# MSP430.net
KiCad netlist of a schematic drawn in Altium Designer
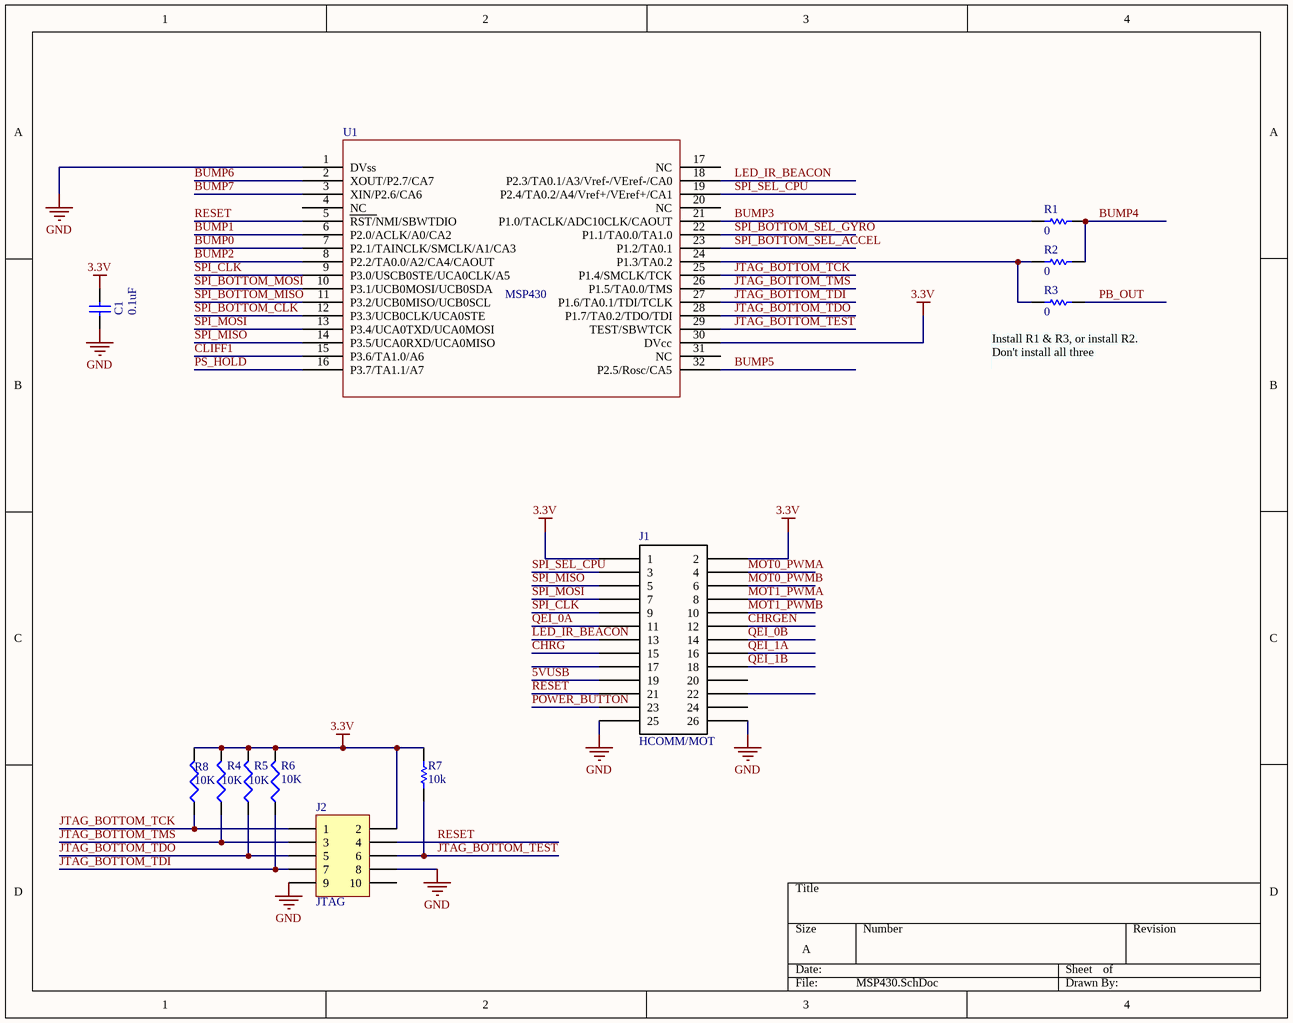
[diagram p0: MSP430.SchDoc]

(export (version "E")
  (design (tool "Eeschema 10.0.6"))
  (components
    (comp (ref "C1")
      (value "0.1uF")
      (footprint "CAPC1005L")
      (description "Capacitor (Semiconductor SIM Model)")
      (fields (field (name "Comment") "Cap Semi") (field (name "PUBLISHER") "Altium Limited"))
      (libsource (lib "Miscellaneous Devices") (part "Cap Semi"))
    )
    (comp (ref "J1")
      (value "HCOMM/MOT")
      (footprint "HeaderSM 13x2")
      (description "Header, 2X20, 50mil, IDC")
      (libsource (lib "mrone") (part "HCOMM/HMOT"))
    )
    (comp (ref "J2")
      (value "JTAG")
      (footprint "HDR2X5")
      (description "Header, 5-Pin, Dual row")
      (fields (field (name "PUBLISHER") "Altium Limited"))
      (libsource (lib "Miscellaneous Connectors") (part "Header 5X2"))
    )
    (comp (ref "R1")
      (value "0")
      (footprint "RESC1608L")
      (description "Semiconductor Resistor")
      (fields (field (name "Comment") "Res Semi") (field (name "PUBLISHER") "Altium Limited"))
      (libsource (lib "Miscellaneous Devices") (part "Res Semi"))
    )
    (comp (ref "R2")
      (value "0")
      (footprint "RESC1608L")
      (description "Semiconductor Resistor")
      (fields (field (name "Comment") "Res Semi") (field (name "PUBLISHER") "Altium Limited"))
      (libsource (lib "Miscellaneous Devices") (part "Res Semi"))
    )
    (comp (ref "R3")
      (value "0")
      (footprint "RESC1608L")
      (description "Semiconductor Resistor")
      (fields (field (name "Comment") "Res Semi") (field (name "PUBLISHER") "Altium Limited"))
      (libsource (lib "Miscellaneous Devices") (part "Res Semi"))
    )
    (comp (ref "R4")
      (value "10K")
      (footprint "RESC1608L")
      (description "Resistor")
      (fields (field (name "Comment") "Res3") (field (name "PUBLISHER") "Altium Limited"))
      (libsource (lib "Miscellaneous Devices") (part "Res3"))
    )
    (comp (ref "R5")
      (value "10K")
      (footprint "RESC1608L")
      (description "Resistor")
      (fields (field (name "Comment") "Res3") (field (name "PUBLISHER") "Altium Limited"))
      (libsource (lib "Miscellaneous Devices") (part "Res3"))
    )
    (comp (ref "R6")
      (value "10K")
      (footprint "RESC1608L")
      (description "Resistor")
      (fields (field (name "Comment") "Res3") (field (name "PUBLISHER") "Altium Limited"))
      (libsource (lib "Miscellaneous Devices") (part "Res3"))
    )
    (comp (ref "R7")
      (value "10k")
      (footprint "RESC1608L")
      (description "Semiconductor Resistor")
      (fields (field (name "Comment") "Res Semi") (field (name "PUBLISHER") "Altium Limited"))
      (libsource (lib "Miscellaneous Devices") (part "Res Semi"))
    )
    (comp (ref "R8")
      (value "10K")
      (footprint "RESC1608L")
      (description "Resistor")
      (fields (field (name "Comment") "Res3") (field (name "PUBLISHER") "Altium Limited"))
      (libsource (lib "Miscellaneous Devices") (part "Res3"))
    )
    (comp (ref "U1")
      (value "MSP430")
      (footprint "MSP430_32PIN")
      (libsource (lib "mrone") (part "MSP430_32pin"))
    )
  )
  (nets
    (net (code "1") (name "/5VUSB") (class "Default")
      (node (ref "J1") (pin "19") (pinfunction "19_19") (pintype "passive"))
    )
    (net (code "2") (name "/BUMP0") (class "Default")
      (node (ref "U1") (pin "7") (pinfunction "P2.1/TAINCLK/SMCLK/A1/CA3_7") (pintype "passive"))
    )
    (net (code "3") (name "/BUMP1") (class "Default")
      (node (ref "U1") (pin "6") (pinfunction "P2.0/ACLK/A0/CA2_6") (pintype "passive"))
    )
    (net (code "4") (name "/BUMP2") (class "Default")
      (node (ref "U1") (pin "8") (pinfunction "P2.2/TA0.0/A2/CA4/CAOUT_8") (pintype "passive"))
    )
    (net (code "5") (name "/BUMP3") (class "Default")
      (node (ref "R1") (pin "2") (pinfunction "2_2") (pintype "passive"))
      (node (ref "U1") (pin "21") (pinfunction "P1.0/TACLK/ADC10CLK/CAOUT_21") (pintype "passive"))
    )
    (net (code "6") (name "/BUMP4") (class "Default")
      (node (ref "R1") (pin "1") (pinfunction "1_1") (pintype "passive"))
      (node (ref "R2") (pin "1") (pinfunction "1_1") (pintype "passive"))
    )
    (net (code "7") (name "/BUMP5") (class "Default")
      (node (ref "U1") (pin "32") (pinfunction "P2.5/Rosc/CA5_32") (pintype "passive"))
    )
    (net (code "8") (name "/BUMP6") (class "Default")
      (node (ref "U1") (pin "2") (pinfunction "XOUT/P2.7/CA7_2") (pintype "passive"))
    )
    (net (code "9") (name "/BUMP7") (class "Default")
      (node (ref "U1") (pin "3") (pinfunction "XIN/P2.6/CA6_3") (pintype "passive"))
    )
    (net (code "10") (name "/CHRG") (class "Default")
      (node (ref "J1") (pin "15") (pinfunction "15_15") (pintype "passive"))
    )
    (net (code "11") (name "/CHRGEN") (class "Default")
      (node (ref "J1") (pin "12") (pinfunction "12_12") (pintype "passive"))
    )
    (net (code "12") (name "/CLIFF1") (class "Default")
      (node (ref "U1") (pin "15") (pinfunction "P3.6/TA1.0/A6_15") (pintype "passive"))
    )
    (net (code "13") (name "/JTAG_BOTTOM_TCK") (class "Default")
      (node (ref "J2") (pin "1") (pinfunction "1_1") (pintype "passive"))
      (node (ref "R8") (pin "1") (pinfunction "1_1") (pintype "passive"))
      (node (ref "U1") (pin "25") (pinfunction "P1.4/SMCLK/TCK_25") (pintype "passive"))
    )
    (net (code "14") (name "/JTAG_BOTTOM_TDI") (class "Default")
      (node (ref "J2") (pin "7") (pinfunction "7_7") (pintype "passive"))
      (node (ref "R6") (pin "1") (pinfunction "1_1") (pintype "passive"))
      (node (ref "U1") (pin "27") (pinfunction "P1.6/TA0.1/TDI/TCLK_27") (pintype "passive"))
    )
    (net (code "15") (name "/JTAG_BOTTOM_TDO") (class "Default")
      (node (ref "J2") (pin "5") (pinfunction "5_5") (pintype "passive"))
      (node (ref "R5") (pin "1") (pinfunction "1_1") (pintype "passive"))
      (node (ref "U1") (pin "28") (pinfunction "P1.7/TA0.2/TDO/TDI_28") (pintype "passive"))
    )
    (net (code "16") (name "/JTAG_BOTTOM_TEST") (class "Default")
      (node (ref "J2") (pin "6") (pinfunction "6_6") (pintype "passive"))
      (node (ref "R7") (pin "1") (pinfunction "1_1") (pintype "passive"))
      (node (ref "U1") (pin "29") (pinfunction "TEST/SBWTCK_29") (pintype "passive"))
    )
    (net (code "17") (name "/JTAG_BOTTOM_TMS") (class "Default")
      (node (ref "J2") (pin "3") (pinfunction "3_3") (pintype "passive"))
      (node (ref "R4") (pin "1") (pinfunction "1_1") (pintype "passive"))
      (node (ref "U1") (pin "26") (pinfunction "P1.5/TA0.0/TMS_26") (pintype "passive"))
    )
    (net (code "18") (name "/LED_IR_BEACON") (class "Default")
      (node (ref "J1") (pin "13") (pinfunction "13_13") (pintype "passive"))
      (node (ref "U1") (pin "18") (pinfunction "P2.3/TA0.1/A3/Vref-/VEref-/CA0_18") (pintype "passive"))
    )
    (net (code "19") (name "/MOT0_PWMA") (class "Default")
      (node (ref "J1") (pin "4") (pinfunction "4_4") (pintype "passive"))
    )
    (net (code "20") (name "/MOT0_PWMB") (class "Default")
      (node (ref "J1") (pin "6") (pinfunction "6_6") (pintype "passive"))
    )
    (net (code "21") (name "/MOT1_PWMA") (class "Default")
      (node (ref "J1") (pin "8") (pinfunction "8_8") (pintype "passive"))
    )
    (net (code "22") (name "/MOT1_PWMB") (class "Default")
      (node (ref "J1") (pin "10") (pinfunction "10_10") (pintype "passive"))
    )
    (net (code "23") (name "/PB_OUT") (class "Default")
      (node (ref "R3") (pin "1") (pinfunction "1_1") (pintype "passive"))
    )
    (net (code "24") (name "/POWER_BUTTON") (class "Default")
      (node (ref "J1") (pin "23") (pinfunction "23_23") (pintype "passive"))
    )
    (net (code "25") (name "/PS_HOLD") (class "Default")
      (node (ref "U1") (pin "16") (pinfunction "P3.7/TA1.1/A7_16") (pintype "passive"))
    )
    (net (code "26") (name "/QEI_0A") (class "Default")
      (node (ref "J1") (pin "11") (pinfunction "11_11") (pintype "passive"))
    )
    (net (code "27") (name "/QEI_0B") (class "Default")
      (node (ref "J1") (pin "14") (pinfunction "14_14") (pintype "passive"))
    )
    (net (code "28") (name "/QEI_1A") (class "Default")
      (node (ref "J1") (pin "16") (pinfunction "16_16") (pintype "passive"))
    )
    (net (code "29") (name "/QEI_1B") (class "Default")
      (node (ref "J1") (pin "18") (pinfunction "18_18") (pintype "passive"))
    )
    (net (code "30") (name "/RESET") (class "Default")
      (node (ref "J1") (pin "21") (pinfunction "21_21") (pintype "passive"))
      (node (ref "J2") (pin "4") (pinfunction "4_4") (pintype "passive"))
      (node (ref "U1") (pin "5") (pinfunction "RST/NMI/SBWTDIO_5") (pintype "passive"))
    )
    (net (code "31") (name "/SPI_BOTTOM_CLK") (class "Default")
      (node (ref "U1") (pin "12") (pinfunction "P3.3/UCB0CLK/UCA0STE_12") (pintype "passive"))
    )
    (net (code "32") (name "/SPI_BOTTOM_MISO") (class "Default")
      (node (ref "U1") (pin "11") (pinfunction "P3.2/UCB0MISO/UCB0SCL_11") (pintype "passive"))
    )
    (net (code "33") (name "/SPI_BOTTOM_MOSI") (class "Default")
      (node (ref "U1") (pin "10") (pinfunction "P3.1/UCB0MOSI/UCB0SDA_10") (pintype "passive"))
    )
    (net (code "34") (name "/SPI_BOTTOM_SEL_ACCEL") (class "Default")
      (node (ref "U1") (pin "23") (pinfunction "P1.2/TA0.1_23") (pintype "passive"))
    )
    (net (code "35") (name "/SPI_BOTTOM_SEL_GYRO") (class "Default")
      (node (ref "U1") (pin "22") (pinfunction "P1.1/TA0.0/TA1.0_22") (pintype "passive"))
    )
    (net (code "36") (name "/SPI_CLK") (class "Default")
      (node (ref "J1") (pin "9") (pinfunction "9_9") (pintype "passive"))
      (node (ref "U1") (pin "9") (pinfunction "P3.0/USCB0STE/UCA0CLK/A5_9") (pintype "passive"))
    )
    (net (code "37") (name "/SPI_MISO") (class "Default")
      (node (ref "J1") (pin "5") (pinfunction "5_5") (pintype "passive"))
      (node (ref "U1") (pin "14") (pinfunction "P3.5/UCA0RXD/UCA0MISO_14") (pintype "passive"))
    )
    (net (code "38") (name "/SPI_MOSI") (class "Default")
      (node (ref "J1") (pin "7") (pinfunction "7_7") (pintype "passive"))
      (node (ref "U1") (pin "13") (pinfunction "P3.4/UCA0TXD/UCA0MOSI_13") (pintype "passive"))
    )
    (net (code "39") (name "/SPI_SEL_CPU") (class "Default")
      (node (ref "J1") (pin "3") (pinfunction "3_3") (pintype "passive"))
      (node (ref "U1") (pin "19") (pinfunction "P2.4/TA0.2/A4/Vref+/VEref+/CA1_19") (pintype "passive"))
    )
    (net (code "40") (name "3.3V") (class "Default")
      (node (ref "C1") (pin "2") (pinfunction "2_2") (pintype "passive"))
      (node (ref "J1") (pin "1") (pinfunction "1_1") (pintype "passive"))
      (node (ref "J1") (pin "2") (pinfunction "2_2") (pintype "passive"))
      (node (ref "J2") (pin "2") (pinfunction "2_2") (pintype "passive"))
      (node (ref "R4") (pin "2") (pinfunction "2_2") (pintype "passive"))
      (node (ref "R5") (pin "2") (pinfunction "2_2") (pintype "passive"))
      (node (ref "R6") (pin "2") (pinfunction "2_2") (pintype "passive"))
      (node (ref "R7") (pin "2") (pinfunction "2_2") (pintype "passive"))
      (node (ref "R8") (pin "2") (pinfunction "2_2") (pintype "passive"))
      (node (ref "U1") (pin "30") (pinfunction "DVcc_30") (pintype "passive"))
    )
    (net (code "41") (name "GND") (class "Default")
      (node (ref "C1") (pin "1") (pinfunction "1_1") (pintype "passive"))
      (node (ref "J1") (pin "25") (pinfunction "25_25") (pintype "passive"))
      (node (ref "J1") (pin "26") (pinfunction "26_26") (pintype "passive"))
      (node (ref "J2") (pin "8") (pinfunction "8_8") (pintype "passive"))
      (node (ref "J2") (pin "9") (pinfunction "9_9") (pintype "passive"))
      (node (ref "U1") (pin "1") (pinfunction "DVss_1") (pintype "passive"))
    )
    (net (code "42") (name "Net-(U1-P1.3{slash}TA0.2)") (class "Default")
      (node (ref "R2") (pin "2") (pinfunction "2_2") (pintype "passive"))
      (node (ref "R3") (pin "2") (pinfunction "2_2") (pintype "passive"))
      (node (ref "U1") (pin "24") (pinfunction "P1.3/TA0.2_24") (pintype "passive"))
    )
    (net (code "43") (name "unconnected-(J1-Pad17)") (class "Default")
      (node (ref "J1") (pin "17") (pinfunction "17_17") (pintype "passive"))
    )
    (net (code "44") (name "unconnected-(J1-Pad20)") (class "Default")
      (node (ref "J1") (pin "20") (pinfunction "20_20") (pintype "passive"))
    )
    (net (code "45") (name "unconnected-(J1-Pad22)") (class "Default")
      (node (ref "J1") (pin "22") (pinfunction "22_22") (pintype "passive"))
    )
    (net (code "46") (name "unconnected-(J1-Pad24)") (class "Default")
      (node (ref "J1") (pin "24") (pinfunction "24_24") (pintype "passive"))
    )
    (net (code "47") (name "unconnected-(J2-Pad10)") (class "Default")
      (node (ref "J2") (pin "10") (pinfunction "10_10") (pintype "passive"))
    )
    (net (code "48") (name "unconnected-(U1-NC-Pad4)") (class "Default")
      (node (ref "U1") (pin "4") (pinfunction "NC_4") (pintype "passive"))
    )
    (net (code "49") (name "unconnected-(U1-NC-Pad17)") (class "Default")
      (node (ref "U1") (pin "17") (pinfunction "NC_17") (pintype "passive"))
    )
    (net (code "50") (name "unconnected-(U1-NC-Pad20)") (class "Default")
      (node (ref "U1") (pin "20") (pinfunction "NC_20") (pintype "passive"))
    )
    (net (code "51") (name "unconnected-(U1-NC-Pad31)") (class "Default")
      (node (ref "U1") (pin "31") (pinfunction "NC_31") (pintype "passive"))
    )
  )
)
